# SIT1533_Oscillator.net
KiCad netlist of a schematic drawn in Altium Designer
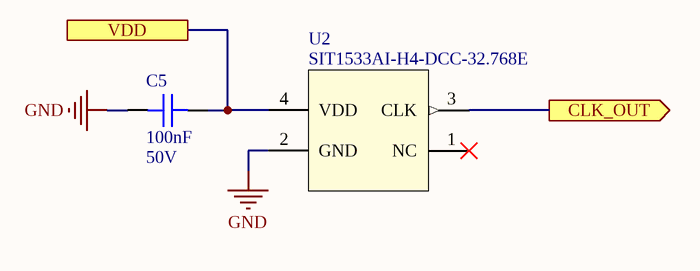
[diagram p0: SIT1533_Oscillator.SchDoc]

(export (version "E")
  (design (tool "Eeschema 10.0.6"))
  (components
    (comp (ref "C5")
      (value "CAP CER 0.1UF 50V X7R 0402")
      (footprint "C0402")
      (description "0.1µF ±10% 50V Ceramic Capacitor X7R 0402 (1005 Metric)")
      (fields
        (field (name "MANUFACTURER") "TDK")
        (field (name "MANUFACTURER PART NUMBER") "CGA2B3X7R1H104K050BB")
        (field (name "CAPACITANCE") "100nF")
        (field (name "VOLTAGE") "50V")
      )
      (libsource (lib "Control_Board_Model") (part "CAP CER 0.1UF 50V X7R 0402"))
    )
    (comp (ref "U2")
      (value "IC SIT1533AI-H4-DCC-32.768E MEMS OSC XO 32.7680KHZ LVCMOS")
      (footprint "XTAL4_SiT1533_SIT")
      (description "32.768kHz XO (Standard) LVCMOS Oscillator 1.5V ~ 3.63V  4-SMD, No Lead")
      (fields
        (field (name "MANUFACTURER") "SiTime")
        (field (name "MANUFACTURER PART NUMBER") "SIT1533AI-H4-DCC-32.768E")
      )
      (libsource (lib "BLDC_Motor_Driver") (part "IC SIT1533AI-H4-DCC-32.768E MEMS OSC XO 32.7680KHZ LVCMOS"))
    )
  )
  (nets
    (net (code "1") (name "/CLK_OUT") (class "Default")
      (node (ref "U2") (pin "3") (pinfunction "CLK_3") (pintype "output"))
    )
    (net (code "2") (name "/VDD") (class "Default")
      (node (ref "C5") (pin "2") (pinfunction "2_2") (pintype "passive"))
      (node (ref "U2") (pin "4") (pinfunction "VDD_4") (pintype "power_in"))
    )
    (net (code "3") (name "GND") (class "Default")
      (node (ref "C5") (pin "1") (pinfunction "1_1") (pintype "passive"))
      (node (ref "U2") (pin "2") (pinfunction "GND_2") (pintype "power_in"))
    )
    (net (code "4") (name "unconnected-(U2-NC-Pad1)") (class "Default")
      (node (ref "U2") (pin "1") (pinfunction "NC_1") (pintype "passive+no_connect"))
    )
  )
)
